# DIGITAL_OUTPUTS_BLOCK_A.net
KiCad netlist of a schematic drawn in Altium Designer
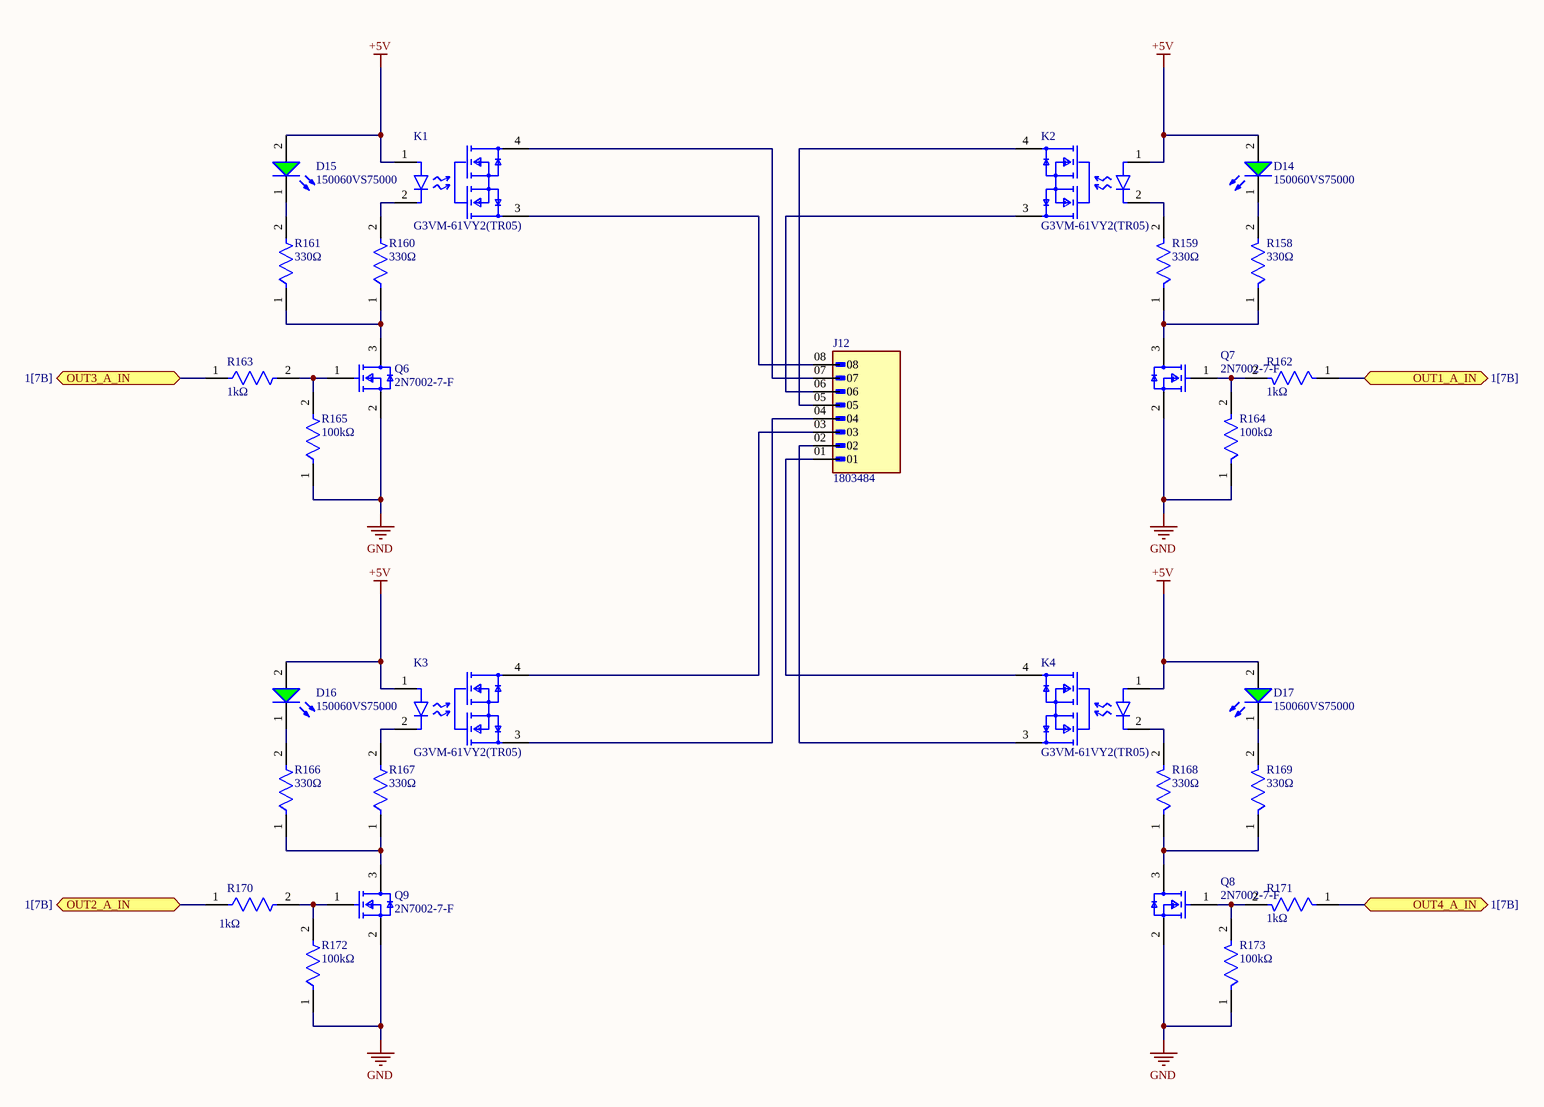
[diagram p0: DIGITAL_OUTPUTS_BLOCK_A.SchDoc]

(export (version "E")
  (design (tool "Eeschema 10.0.6"))
  (components
    (comp (ref "D14")
      (value "150060VS75000")
      (footprint "WL-SMCW_0603_150060xx75000")
      (libsource (lib "Altium Content Vault") (part "LED_Green_2A-1K"))
    )
    (comp (ref "D15")
      (value "150060VS75000")
      (footprint "WL-SMCW_0603_150060xx75000")
      (libsource (lib "Altium Content Vault") (part "LED_Green_2A-1K"))
    )
    (comp (ref "D16")
      (value "150060VS75000")
      (footprint "WL-SMCW_0603_150060xx75000")
      (libsource (lib "Altium Content Vault") (part "LED_Green_2A-1K"))
    )
    (comp (ref "D17")
      (value "150060VS75000")
      (footprint "WL-SMCW_0603_150060xx75000")
      (libsource (lib "Altium Content Vault") (part "LED_Green_2A-1K"))
    )
    (comp (ref "J12")
      (value "1803484")
      (footprint "1803484:PHOENIX_1803484")
      (fields (field (name "MF") "{'manufacturer': u'Phoenix Contact'}"))
      (libsource (lib "*") (part "1803484"))
    )
    (comp (ref "K1")
      (value "G3VM-61VY2(TR05)")
      (footprint "FP-G3VM-61VY2_TR05-MFG")
      (description "SSR RELAY SPST-NO 500MA 0-60V")
      (libsource (lib "Altium Content Vault") (part "39108d2c2fe9c6c4263f1aa8ae40286"))
    )
    (comp (ref "K2")
      (value "G3VM-61VY2(TR05)")
      (footprint "FP-G3VM-61VY2_TR05-MFG")
      (description "SSR RELAY SPST-NO 500MA 0-60V")
      (libsource (lib "Altium Content Vault") (part "39108d2c2fe9c6c4263f1aa8ae40286"))
    )
    (comp (ref "K3")
      (value "G3VM-61VY2(TR05)")
      (footprint "FP-G3VM-61VY2_TR05-MFG")
      (description "SSR RELAY SPST-NO 500MA 0-60V")
      (libsource (lib "Altium Content Vault") (part "39108d2c2fe9c6c4263f1aa8ae40286"))
    )
    (comp (ref "K4")
      (value "G3VM-61VY2(TR05)")
      (footprint "FP-G3VM-61VY2_TR05-MFG")
      (description "SSR RELAY SPST-NO 500MA 0-60V")
      (libsource (lib "Altium Content Vault") (part "39108d2c2fe9c6c4263f1aa8ae40286"))
    )
    (comp (ref "Q6")
      (value "2N7002-7-F")
      (footprint "FP-SOT23-IPC_A")
      (description "MOSFET N-CH 60V 115MA SOT23-3")
      (fields (field (name "VOLTAGE") "60V"))
      (libsource (lib "Altium Content Vault") (part "3b9c635fedb024a5347a57b145af9cc"))
    )
    (comp (ref "Q7")
      (value "2N7002-7-F")
      (footprint "FP-SOT23-IPC_A")
      (description "MOSFET N-CH 60V 115MA SOT23-3")
      (fields (field (name "VOLTAGE") "60V"))
      (libsource (lib "Altium Content Vault") (part "3b9c635fedb024a5347a57b145af9cc"))
    )
    (comp (ref "Q8")
      (value "2N7002-7-F")
      (footprint "FP-SOT23-IPC_A")
      (description "MOSFET N-CH 60V 115MA SOT23-3")
      (fields (field (name "VOLTAGE") "60V"))
      (libsource (lib "Altium Content Vault") (part "3b9c635fedb024a5347a57b145af9cc"))
    )
    (comp (ref "Q9")
      (value "2N7002-7-F")
      (footprint "FP-SOT23-IPC_A")
      (description "MOSFET N-CH 60V 115MA SOT23-3")
      (fields (field (name "VOLTAGE") "60V"))
      (libsource (lib "Altium Content Vault") (part "3b9c635fedb024a5347a57b145af9cc"))
    )
    (comp (ref "R158")
      (value "CRCW0603330RFKEA")
      (footprint "FP-CRCW0603-e3-MFG")
      (description "RES Thick Film, 330Ω, 1%, 0.1W, 100ppm/°C, 0603")
      (fields (field (name "TOLERANCE") "1%") (field (name "RESISTANCE") "330Ω"))
      (libsource (lib "Altium Content Vault") (part "1029c3af85768c4190bb7ad29bc67b5"))
    )
    (comp (ref "R159")
      (value "CRCW0603330RFKEA")
      (footprint "FP-CRCW0603-e3-MFG")
      (description "RES Thick Film, 330Ω, 1%, 0.1W, 100ppm/°C, 0603")
      (fields (field (name "TOLERANCE") "1%") (field (name "RESISTANCE") "330Ω"))
      (libsource (lib "Altium Content Vault") (part "1029c3af85768c4190bb7ad29bc67b5"))
    )
    (comp (ref "R160")
      (value "CRCW0603330RFKEA")
      (footprint "FP-CRCW0603-e3-MFG")
      (description "RES Thick Film, 330Ω, 1%, 0.1W, 100ppm/°C, 0603")
      (fields (field (name "TOLERANCE") "1%") (field (name "RESISTANCE") "330Ω"))
      (libsource (lib "Altium Content Vault") (part "1029c3af85768c4190bb7ad29bc67b5"))
    )
    (comp (ref "R161")
      (value "CRCW0603330RFKEA")
      (footprint "FP-CRCW0603-e3-MFG")
      (description "RES Thick Film, 330Ω, 1%, 0.1W, 100ppm/°C, 0603")
      (fields (field (name "TOLERANCE") "1%") (field (name "RESISTANCE") "330Ω"))
      (libsource (lib "Altium Content Vault") (part "1029c3af85768c4190bb7ad29bc67b5"))
    )
    (comp (ref "R162")
      (value "AC0603FR-071KL")
      (footprint "FP-AC0603-IPC_B")
      (description "RES 1kΩ 1.00% 0.1W 0603")
      (fields (field (name "TOLERANCE") "1%") (field (name "RESISTANCE") "1kΩ"))
      (libsource (lib "Altium Content Vault") (part "1029c3af85768c4190bb7ad29bc67b5"))
    )
    (comp (ref "R163")
      (value "AC0603FR-071KL")
      (footprint "FP-AC0603-IPC_B")
      (description "RES 1kΩ 1.00% 0.1W 0603")
      (fields (field (name "TOLERANCE") "1%") (field (name "RESISTANCE") "1kΩ"))
      (libsource (lib "Altium Content Vault") (part "1029c3af85768c4190bb7ad29bc67b5"))
    )
    (comp (ref "R164")
      (value "CRCW0603100KFKEC")
      (footprint "FP-CRCW0603-e3-IPC_B")
      (description "RES Thick Film, 100kΩ, 1%, 0.1W, 100ppm/°C, 0603")
      (fields (field (name "RESISTANCE") "100kΩ") (field (name "TOLERANCE") "1%"))
      (libsource (lib "Altium Content Vault") (part "1029c3af85768c4190bb7ad29bc67b5"))
    )
    (comp (ref "R165")
      (value "CRCW0603100KFKEC")
      (footprint "FP-CRCW0603-e3-IPC_B")
      (description "RES Thick Film, 100kΩ, 1%, 0.1W, 100ppm/°C, 0603")
      (fields (field (name "RESISTANCE") "100kΩ") (field (name "TOLERANCE") "1%"))
      (libsource (lib "Altium Content Vault") (part "1029c3af85768c4190bb7ad29bc67b5"))
    )
    (comp (ref "R166")
      (value "CRCW0603330RFKEA")
      (footprint "FP-CRCW0603-e3-MFG")
      (description "RES Thick Film, 330Ω, 1%, 0.1W, 100ppm/°C, 0603")
      (fields (field (name "TOLERANCE") "1%") (field (name "RESISTANCE") "330Ω"))
      (libsource (lib "Altium Content Vault") (part "1029c3af85768c4190bb7ad29bc67b5"))
    )
    (comp (ref "R167")
      (value "CRCW0603330RFKEA")
      (footprint "FP-CRCW0603-e3-MFG")
      (description "RES Thick Film, 330Ω, 1%, 0.1W, 100ppm/°C, 0603")
      (fields (field (name "TOLERANCE") "1%") (field (name "RESISTANCE") "330Ω"))
      (libsource (lib "Altium Content Vault") (part "1029c3af85768c4190bb7ad29bc67b5"))
    )
    (comp (ref "R168")
      (value "CRCW0603330RFKEA")
      (footprint "FP-CRCW0603-e3-MFG")
      (description "RES Thick Film, 330Ω, 1%, 0.1W, 100ppm/°C, 0603")
      (fields (field (name "TOLERANCE") "1%") (field (name "RESISTANCE") "330Ω"))
      (libsource (lib "Altium Content Vault") (part "1029c3af85768c4190bb7ad29bc67b5"))
    )
    (comp (ref "R169")
      (value "CRCW0603330RFKEA")
      (footprint "FP-CRCW0603-e3-MFG")
      (description "RES Thick Film, 330Ω, 1%, 0.1W, 100ppm/°C, 0603")
      (fields (field (name "TOLERANCE") "1%") (field (name "RESISTANCE") "330Ω"))
      (libsource (lib "Altium Content Vault") (part "1029c3af85768c4190bb7ad29bc67b5"))
    )
    (comp (ref "R170")
      (value "AC0603FR-071KL")
      (footprint "FP-AC0603-IPC_B")
      (description "RES 1kΩ 1.00% 0.1W 0603")
      (fields (field (name "TOLERANCE") "1%") (field (name "RESISTANCE") "1kΩ"))
      (libsource (lib "Altium Content Vault") (part "1029c3af85768c4190bb7ad29bc67b5"))
    )
    (comp (ref "R171")
      (value "AC0603FR-071KL")
      (footprint "FP-AC0603-IPC_B")
      (description "RES 1kΩ 1.00% 0.1W 0603")
      (fields (field (name "TOLERANCE") "1%") (field (name "RESISTANCE") "1kΩ"))
      (libsource (lib "Altium Content Vault") (part "1029c3af85768c4190bb7ad29bc67b5"))
    )
    (comp (ref "R172")
      (value "CRCW0603100KFKEC")
      (footprint "FP-CRCW0603-e3-IPC_B")
      (description "RES Thick Film, 100kΩ, 1%, 0.1W, 100ppm/°C, 0603")
      (fields (field (name "RESISTANCE") "100kΩ") (field (name "TOLERANCE") "1%"))
      (libsource (lib "Altium Content Vault") (part "1029c3af85768c4190bb7ad29bc67b5"))
    )
    (comp (ref "R173")
      (value "CRCW0603100KFKEC")
      (footprint "FP-CRCW0603-e3-IPC_B")
      (description "RES Thick Film, 100kΩ, 1%, 0.1W, 100ppm/°C, 0603")
      (fields (field (name "RESISTANCE") "100kΩ") (field (name "TOLERANCE") "1%"))
      (libsource (lib "Altium Content Vault") (part "1029c3af85768c4190bb7ad29bc67b5"))
    )
  )
  (nets
    (net (code "1") (name "+5V") (class "Default")
      (node (ref "D14") (pin "2") (pinfunction "A_2") (pintype "passive"))
      (node (ref "D15") (pin "2") (pinfunction "A_2") (pintype "passive"))
      (node (ref "D16") (pin "2") (pinfunction "A_2") (pintype "passive"))
      (node (ref "D17") (pin "2") (pinfunction "A_2") (pintype "passive"))
      (node (ref "K1") (pin "1") (pinfunction "A_1") (pintype "passive"))
      (node (ref "K2") (pin "1") (pinfunction "A_1") (pintype "passive"))
      (node (ref "K3") (pin "1") (pinfunction "A_1") (pintype "passive"))
      (node (ref "K4") (pin "1") (pinfunction "A_1") (pintype "passive"))
    )
    (net (code "2") (name "/OUT1_A_IN") (class "Default")
      (node (ref "R162") (pin "1") (pinfunction "1_1") (pintype "passive"))
    )
    (net (code "3") (name "/OUT2_A_IN") (class "Default")
      (node (ref "R170") (pin "1") (pinfunction "1_1") (pintype "passive"))
    )
    (net (code "4") (name "/OUT3_A_IN") (class "Default")
      (node (ref "R163") (pin "1") (pinfunction "1_1") (pintype "passive"))
    )
    (net (code "5") (name "/OUT4_A_IN") (class "Default")
      (node (ref "R171") (pin "1") (pinfunction "1_1") (pintype "passive"))
    )
    (net (code "6") (name "GND") (class "Default")
      (node (ref "Q6") (pin "2") (pinfunction "S_2") (pintype "passive"))
      (node (ref "Q7") (pin "2") (pinfunction "S_2") (pintype "passive"))
      (node (ref "Q8") (pin "2") (pinfunction "S_2") (pintype "passive"))
      (node (ref "Q9") (pin "2") (pinfunction "S_2") (pintype "passive"))
      (node (ref "R164") (pin "1") (pinfunction "1_1") (pintype "passive"))
      (node (ref "R165") (pin "1") (pinfunction "1_1") (pintype "passive"))
      (node (ref "R172") (pin "1") (pinfunction "1_1") (pintype "passive"))
      (node (ref "R173") (pin "1") (pinfunction "1_1") (pintype "passive"))
    )
    (net (code "7") (name "Net-(D14-K)") (class "Default")
      (node (ref "D14") (pin "1") (pinfunction "K_1") (pintype "passive"))
      (node (ref "R158") (pin "2") (pinfunction "2_2") (pintype "passive"))
    )
    (net (code "8") (name "Net-(D15-K)") (class "Default")
      (node (ref "D15") (pin "1") (pinfunction "K_1") (pintype "passive"))
      (node (ref "R161") (pin "2") (pinfunction "2_2") (pintype "passive"))
    )
    (net (code "9") (name "Net-(D16-K)") (class "Default")
      (node (ref "D16") (pin "1") (pinfunction "K_1") (pintype "passive"))
      (node (ref "R166") (pin "2") (pinfunction "2_2") (pintype "passive"))
    )
    (net (code "10") (name "Net-(D17-K)") (class "Default")
      (node (ref "D17") (pin "1") (pinfunction "K_1") (pintype "passive"))
      (node (ref "R169") (pin "2") (pinfunction "2_2") (pintype "passive"))
    )
    (net (code "11") (name "Net-(K1-1_DRAIN)") (class "Default")
      (node (ref "J12") (pin "08") (pinfunction "08_08") (pintype "passive"))
      (node (ref "K1") (pin "3") (pinfunction "1_DRAIN_3") (pintype "passive"))
    )
    (net (code "12") (name "Net-(K1-2_DRAIN)") (class "Default")
      (node (ref "J12") (pin "07") (pinfunction "07_07") (pintype "passive"))
      (node (ref "K1") (pin "4") (pinfunction "2_DRAIN_4") (pintype "passive"))
    )
    (net (code "13") (name "Net-(K1-C)") (class "Default")
      (node (ref "K1") (pin "2") (pinfunction "C_2") (pintype "passive"))
      (node (ref "R160") (pin "2") (pinfunction "2_2") (pintype "passive"))
    )
    (net (code "14") (name "Net-(K2-1_DRAIN)") (class "Default")
      (node (ref "J12") (pin "06") (pinfunction "06_06") (pintype "passive"))
      (node (ref "K2") (pin "3") (pinfunction "1_DRAIN_3") (pintype "passive"))
    )
    (net (code "15") (name "Net-(K2-2_DRAIN)") (class "Default")
      (node (ref "J12") (pin "05") (pinfunction "05_05") (pintype "passive"))
      (node (ref "K2") (pin "4") (pinfunction "2_DRAIN_4") (pintype "passive"))
    )
    (net (code "16") (name "Net-(K2-C)") (class "Default")
      (node (ref "K2") (pin "2") (pinfunction "C_2") (pintype "passive"))
      (node (ref "R159") (pin "2") (pinfunction "2_2") (pintype "passive"))
    )
    (net (code "17") (name "Net-(K3-1_DRAIN)") (class "Default")
      (node (ref "J12") (pin "04") (pinfunction "04_04") (pintype "passive"))
      (node (ref "K3") (pin "3") (pinfunction "1_DRAIN_3") (pintype "passive"))
    )
    (net (code "18") (name "Net-(K3-2_DRAIN)") (class "Default")
      (node (ref "J12") (pin "03") (pinfunction "03_03") (pintype "passive"))
      (node (ref "K3") (pin "4") (pinfunction "2_DRAIN_4") (pintype "passive"))
    )
    (net (code "19") (name "Net-(K3-C)") (class "Default")
      (node (ref "K3") (pin "2") (pinfunction "C_2") (pintype "passive"))
      (node (ref "R167") (pin "2") (pinfunction "2_2") (pintype "passive"))
    )
    (net (code "20") (name "Net-(K4-1_DRAIN)") (class "Default")
      (node (ref "J12") (pin "02") (pinfunction "02_02") (pintype "passive"))
      (node (ref "K4") (pin "3") (pinfunction "1_DRAIN_3") (pintype "passive"))
    )
    (net (code "21") (name "Net-(K4-2_DRAIN)") (class "Default")
      (node (ref "J12") (pin "01") (pinfunction "01_01") (pintype "passive"))
      (node (ref "K4") (pin "4") (pinfunction "2_DRAIN_4") (pintype "passive"))
    )
    (net (code "22") (name "Net-(K4-C)") (class "Default")
      (node (ref "K4") (pin "2") (pinfunction "C_2") (pintype "passive"))
      (node (ref "R168") (pin "2") (pinfunction "2_2") (pintype "passive"))
    )
    (net (code "23") (name "Net-(Q6-D)") (class "Default")
      (node (ref "Q6") (pin "3") (pinfunction "D_3") (pintype "passive"))
      (node (ref "R160") (pin "1") (pinfunction "1_1") (pintype "passive"))
      (node (ref "R161") (pin "1") (pinfunction "1_1") (pintype "passive"))
    )
    (net (code "24") (name "Net-(Q6-G)") (class "Default")
      (node (ref "Q6") (pin "1") (pinfunction "G_1") (pintype "passive"))
      (node (ref "R163") (pin "2") (pinfunction "2_2") (pintype "passive"))
      (node (ref "R165") (pin "2") (pinfunction "2_2") (pintype "passive"))
    )
    (net (code "25") (name "Net-(Q7-D)") (class "Default")
      (node (ref "Q7") (pin "3") (pinfunction "D_3") (pintype "passive"))
      (node (ref "R158") (pin "1") (pinfunction "1_1") (pintype "passive"))
      (node (ref "R159") (pin "1") (pinfunction "1_1") (pintype "passive"))
    )
    (net (code "26") (name "Net-(Q7-G)") (class "Default")
      (node (ref "Q7") (pin "1") (pinfunction "G_1") (pintype "passive"))
      (node (ref "R162") (pin "2") (pinfunction "2_2") (pintype "passive"))
      (node (ref "R164") (pin "2") (pinfunction "2_2") (pintype "passive"))
    )
    (net (code "27") (name "Net-(Q8-D)") (class "Default")
      (node (ref "Q8") (pin "3") (pinfunction "D_3") (pintype "passive"))
      (node (ref "R168") (pin "1") (pinfunction "1_1") (pintype "passive"))
      (node (ref "R169") (pin "1") (pinfunction "1_1") (pintype "passive"))
    )
    (net (code "28") (name "Net-(Q8-G)") (class "Default")
      (node (ref "Q8") (pin "1") (pinfunction "G_1") (pintype "passive"))
      (node (ref "R171") (pin "2") (pinfunction "2_2") (pintype "passive"))
      (node (ref "R173") (pin "2") (pinfunction "2_2") (pintype "passive"))
    )
    (net (code "29") (name "Net-(Q9-D)") (class "Default")
      (node (ref "Q9") (pin "3") (pinfunction "D_3") (pintype "passive"))
      (node (ref "R166") (pin "1") (pinfunction "1_1") (pintype "passive"))
      (node (ref "R167") (pin "1") (pinfunction "1_1") (pintype "passive"))
    )
    (net (code "30") (name "Net-(Q9-G)") (class "Default")
      (node (ref "Q9") (pin "1") (pinfunction "G_1") (pintype "passive"))
      (node (ref "R170") (pin "2") (pinfunction "2_2") (pintype "passive"))
      (node (ref "R172") (pin "2") (pinfunction "2_2") (pintype "passive"))
    )
  )
)
